# ic-mhm-encoder-v2.net
KiCad netlist of a schematic drawn in EAGLE
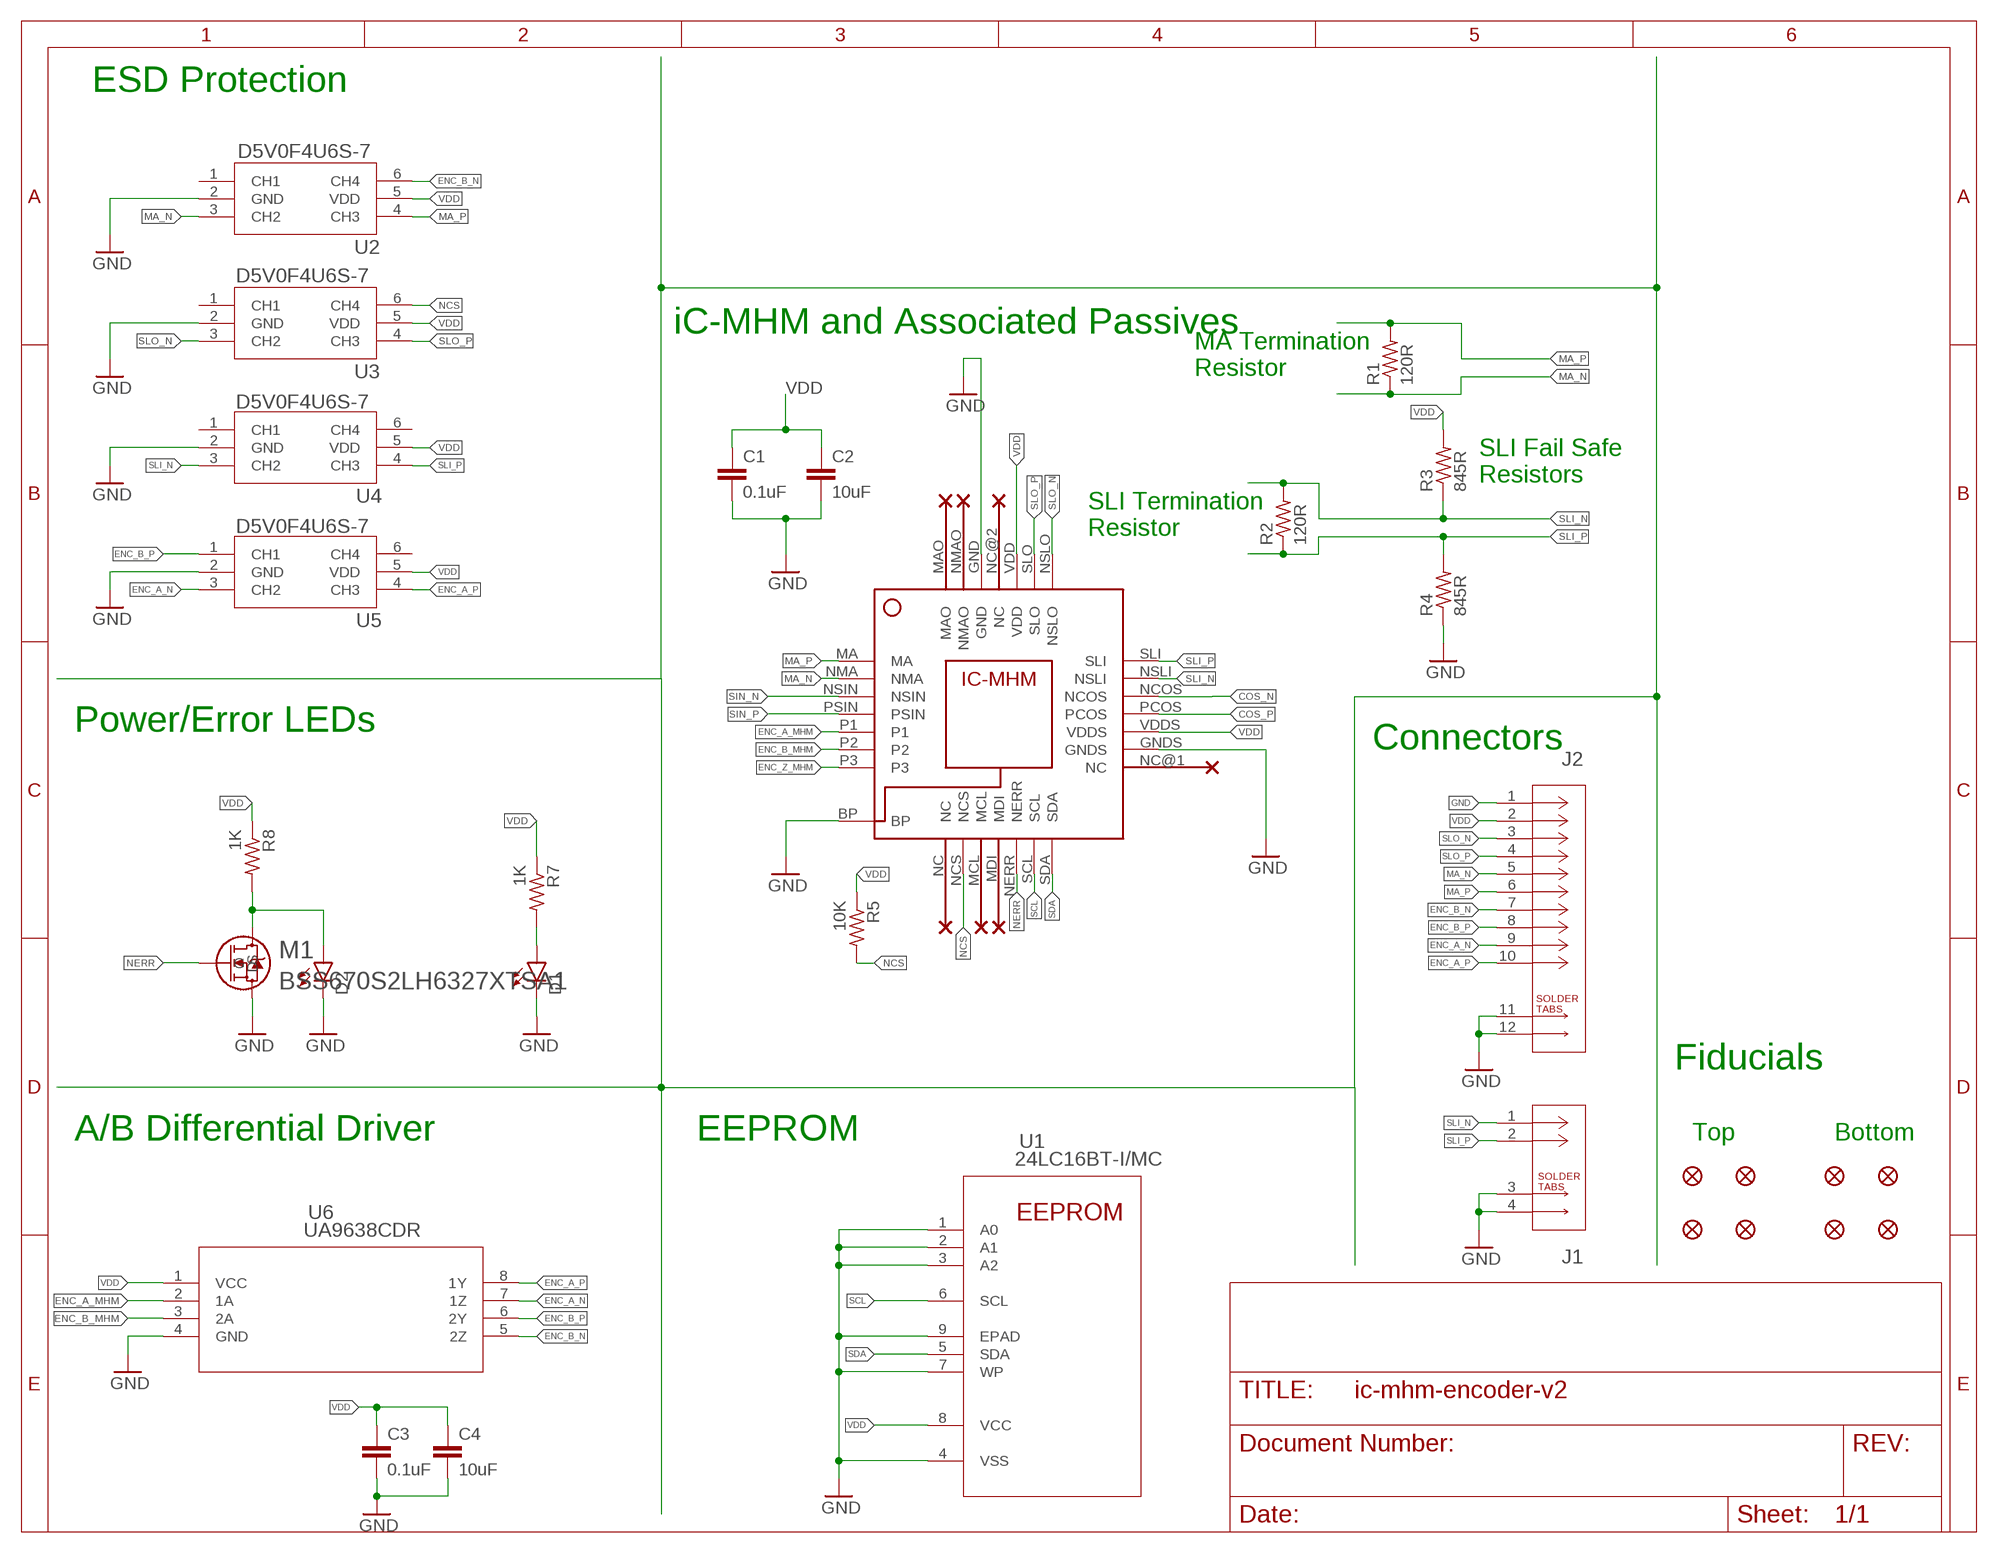
[diagram p0: schematic, sheet 1]

(export (version "E")
  (design (tool "Eeschema 10.0.6"))
  (components
    (comp (ref "C1")
      (value "0.1uF")
      (footprint "eagle-import:C0603")
      (libsource (lib "eagle-import") (part "C-EUC0603"))
    )
    (comp (ref "C2")
      (value "10uF")
      (footprint "eagle-import:C0603")
      (libsource (lib "eagle-import") (part "C-EUC0603"))
    )
    (comp (ref "C3")
      (value "0.1uF")
      (footprint "eagle-import:C0603")
      (libsource (lib "eagle-import") (part "C-EUC0603"))
    )
    (comp (ref "C4")
      (value "10uF")
      (footprint "eagle-import:C0603")
      (libsource (lib "eagle-import") (part "C-EUC0603"))
    )
    (comp (ref "D1")
      (value "LEDSML0603")
      (footprint "eagle-import:SML0603")
      (libsource (lib "eagle-import") (part "LEDSML0603"))
    )
    (comp (ref "D2")
      (value "LEDSML0603")
      (footprint "eagle-import:SML0603")
      (libsource (lib "eagle-import") (part "LEDSML0603"))
    )
    (comp (ref "FID1")
      (value "FIDUCIAL_1MM")
      (footprint "eagle-import:FIDUCIAL_1MM")
      (libsource (lib "eagle-import") (part "FIDUCIAL_1MM"))
    )
    (comp (ref "FID2")
      (value "FIDUCIAL_1MM")
      (footprint "eagle-import:FIDUCIAL_1MM")
      (libsource (lib "eagle-import") (part "FIDUCIAL_1MM"))
    )
    (comp (ref "FID3")
      (value "FIDUCIAL_1MM")
      (footprint "eagle-import:FIDUCIAL_1MM")
      (libsource (lib "eagle-import") (part "FIDUCIAL_1MM"))
    )
    (comp (ref "FID4")
      (value "FIDUCIAL_1MM")
      (footprint "eagle-import:FIDUCIAL_1MM")
      (libsource (lib "eagle-import") (part "FIDUCIAL_1MM"))
    )
    (comp (ref "FID5")
      (value "FIDUCIAL_1MM")
      (footprint "eagle-import:FIDUCIAL_1MM")
      (libsource (lib "eagle-import") (part "FIDUCIAL_1MM"))
    )
    (comp (ref "FID6")
      (value "FIDUCIAL_1MM")
      (footprint "eagle-import:FIDUCIAL_1MM")
      (libsource (lib "eagle-import") (part "FIDUCIAL_1MM"))
    )
    (comp (ref "FID7")
      (value "FIDUCIAL_1MM")
      (footprint "eagle-import:FIDUCIAL_1MM")
      (libsource (lib "eagle-import") (part "FIDUCIAL_1MM"))
    )
    (comp (ref "FID8")
      (value "FIDUCIAL_1MM")
      (footprint "eagle-import:FIDUCIAL_1MM")
      (libsource (lib "eagle-import") (part "FIDUCIAL_1MM"))
    )
    (comp (ref "J1")
      (value "2023960207")
      (footprint "eagle-import:CON_2023960207")
      (fields (field (name "COPYRIGHT") "Copyright (C) 2022 Ultra Librarian. All rights reserved."))
      (libsource (lib "eagle-import") (part "2023960207"))
    )
    (comp (ref "J2")
      (value "2023961007")
      (footprint "eagle-import:CON_2023961007")
      (fields (field (name "COPYRIGHT") "Copyright (C) 2022 Ultra Librarian. All rights reserved."))
      (libsource (lib "eagle-import") (part "2023961007"))
    )
    (comp (ref "M1")
      (value "BSS670S2LH6327XTSA1")
      (footprint "eagle-import:PG-SOT23-3-5_INF")
      (fields (field (name "COPYRIGHT") "Copyright (C) 2021 Ultra Librarian. All rights reserved."))
      (libsource (lib "eagle-import") (part "BSS670S2LH6327XTSA1"))
    )
    (comp (ref "R1")
      (value "120R")
      (footprint "eagle-import:R0603")
      (libsource (lib "eagle-import") (part "R-US_R0603"))
    )
    (comp (ref "R2")
      (value "120R")
      (footprint "eagle-import:R0603")
      (libsource (lib "eagle-import") (part "R-US_R0603"))
    )
    (comp (ref "R3")
      (value "845R")
      (footprint "eagle-import:R0603")
      (libsource (lib "eagle-import") (part "R-US_R0603"))
    )
    (comp (ref "R4")
      (value "845R")
      (footprint "eagle-import:R0603")
      (libsource (lib "eagle-import") (part "R-US_R0603"))
    )
    (comp (ref "R5")
      (value "10K")
      (footprint "eagle-import:R0603")
      (libsource (lib "eagle-import") (part "R-US_R0603"))
    )
    (comp (ref "R7")
      (value "1K")
      (footprint "eagle-import:R0603")
      (libsource (lib "eagle-import") (part "R-US_R0603"))
    )
    (comp (ref "R8")
      (value "1K")
      (footprint "eagle-import:R0603")
      (libsource (lib "eagle-import") (part "R-US_R0603"))
    )
    (comp (ref "U$1")
      (value "IC-MHM")
      (footprint "eagle-import:IC-MHM")
      (libsource (lib "eagle-import") (part "IC-MHM"))
    )
    (comp (ref "U1")
      (value "24LC16BT-I/MC")
      (footprint "eagle-import:DFN8_2X3MC_MCH")
      (fields (field (name "COPYRIGHT") "Copyright (C) 2021 Ultra Librarian. All rights reserved."))
      (libsource (lib "eagle-import") (part "24LC16BT-I/MC"))
    )
    (comp (ref "U2")
      (value "D5V0F4U6S-7")
      (footprint "eagle-import:SOT-363_DIO")
      (fields (field (name "COPYRIGHT") "Copyright (C) 2021 Ultra Librarian. All rights reserved."))
      (libsource (lib "eagle-import") (part "D5V0F4U6S-7"))
    )
    (comp (ref "U3")
      (value "D5V0F4U6S-7")
      (footprint "eagle-import:SOT-363_DIO")
      (fields (field (name "COPYRIGHT") "Copyright (C) 2021 Ultra Librarian. All rights reserved."))
      (libsource (lib "eagle-import") (part "D5V0F4U6S-7"))
    )
    (comp (ref "U4")
      (value "D5V0F4U6S-7")
      (footprint "eagle-import:SOT-363_DIO")
      (fields (field (name "COPYRIGHT") "Copyright (C) 2021 Ultra Librarian. All rights reserved."))
      (libsource (lib "eagle-import") (part "D5V0F4U6S-7"))
    )
    (comp (ref "U5")
      (value "D5V0F4U6S-7")
      (footprint "eagle-import:SOT-363_DIO")
      (fields (field (name "COPYRIGHT") "Copyright (C) 2021 Ultra Librarian. All rights reserved."))
      (libsource (lib "eagle-import") (part "D5V0F4U6S-7"))
    )
    (comp (ref "U6")
      (value "UA9638CDR")
      (footprint "eagle-import:D8")
      (fields (field (name "COPYRIGHT") "Copyright (C) 2022 Ultra Librarian. All rights reserved."))
      (libsource (lib "eagle-import") (part "UA9638CDR"))
    )
  )
  (nets
    (net (code "1") (name "COS_N") (class "Default")
      (node (ref "U$1") (pin "NCOS") (pinfunction "NCOS_NCOS") (pintype "bidirectional"))
    )
    (net (code "2") (name "COS_P") (class "Default")
      (node (ref "U$1") (pin "PCOS") (pinfunction "PCOS_PCOS") (pintype "bidirectional"))
    )
    (net (code "3") (name "ENC_A_MHM") (class "Default")
      (node (ref "U$1") (pin "P1") (pinfunction "P1_P1") (pintype "bidirectional"))
      (node (ref "U6") (pin "2") (pinfunction "1A_2") (pintype "passive"))
    )
    (net (code "4") (name "ENC_A_N") (class "Default")
      (node (ref "J2") (pin "9") (pinfunction "9_9") (pintype "passive"))
      (node (ref "U5") (pin "3") (pinfunction "CH2_3") (pintype "passive"))
      (node (ref "U6") (pin "7") (pinfunction "1Z_7") (pintype "output"))
    )
    (net (code "5") (name "ENC_A_P") (class "Default")
      (node (ref "J2") (pin "10") (pinfunction "10_10") (pintype "passive"))
      (node (ref "U5") (pin "4") (pinfunction "CH3_4") (pintype "passive"))
      (node (ref "U6") (pin "8") (pinfunction "1Y_8") (pintype "output"))
    )
    (net (code "6") (name "ENC_B_MHM") (class "Default")
      (node (ref "U$1") (pin "P2") (pinfunction "P2_P2") (pintype "bidirectional"))
      (node (ref "U6") (pin "3") (pinfunction "2A_3") (pintype "passive"))
    )
    (net (code "7") (name "ENC_B_N") (class "Default")
      (node (ref "J2") (pin "7") (pinfunction "7_7") (pintype "passive"))
      (node (ref "U2") (pin "6") (pinfunction "CH4_6") (pintype "passive"))
      (node (ref "U6") (pin "5") (pinfunction "2Z_5") (pintype "output"))
    )
    (net (code "8") (name "ENC_B_P") (class "Default")
      (node (ref "J2") (pin "8") (pinfunction "8_8") (pintype "passive"))
      (node (ref "U5") (pin "1") (pinfunction "CH1_1") (pintype "passive"))
      (node (ref "U6") (pin "6") (pinfunction "2Y_6") (pintype "output"))
    )
    (net (code "9") (name "ENC_Z_MHM") (class "Default")
      (node (ref "U$1") (pin "P3") (pinfunction "P3_P3") (pintype "bidirectional"))
    )
    (net (code "10") (name "GND") (class "Default")
      (node (ref "C1") (pin "2") (pinfunction "2_2") (pintype "passive"))
      (node (ref "C2") (pin "2") (pinfunction "2_2") (pintype "passive"))
      (node (ref "C3") (pin "2") (pinfunction "2_2") (pintype "passive"))
      (node (ref "C4") (pin "2") (pinfunction "2_2") (pintype "passive"))
      (node (ref "D1") (pin "C") (pinfunction "C_C") (pintype "passive"))
      (node (ref "D2") (pin "C") (pinfunction "C_C") (pintype "passive"))
      (node (ref "J1") (pin "3") (pinfunction "3_3") (pintype "passive"))
      (node (ref "J1") (pin "4") (pinfunction "4_4") (pintype "passive"))
      (node (ref "J2") (pin "1") (pinfunction "1_1") (pintype "passive"))
      (node (ref "J2") (pin "11") (pinfunction "11_11") (pintype "passive"))
      (node (ref "J2") (pin "12") (pinfunction "12_12") (pintype "passive"))
      (node (ref "M1") (pin "2") (pinfunction "S_2") (pintype "passive"))
      (node (ref "R4") (pin "1") (pinfunction "1_1") (pintype "passive"))
      (node (ref "U$1") (pin "BP") (pinfunction "BP_BP") (pintype "bidirectional"))
      (node (ref "U$1") (pin "GND") (pinfunction "GND_GND") (pintype "bidirectional"))
      (node (ref "U$1") (pin "GNDS") (pinfunction "GNDS_GNDS") (pintype "bidirectional"))
      (node (ref "U1") (pin "1") (pinfunction "A0_1") (pintype "input"))
      (node (ref "U1") (pin "2") (pinfunction "A1_2") (pintype "input"))
      (node (ref "U1") (pin "3") (pinfunction "A2_3") (pintype "input"))
      (node (ref "U1") (pin "4") (pinfunction "VSS_4") (pintype "power_in"))
      (node (ref "U1") (pin "7") (pinfunction "WP_7") (pintype "passive"))
      (node (ref "U1") (pin "9") (pinfunction "EPAD_9") (pintype "passive"))
      (node (ref "U2") (pin "2") (pinfunction "GND_2") (pintype "power_in"))
      (node (ref "U3") (pin "2") (pinfunction "GND_2") (pintype "power_in"))
      (node (ref "U4") (pin "2") (pinfunction "GND_2") (pintype "power_in"))
      (node (ref "U5") (pin "2") (pinfunction "GND_2") (pintype "power_in"))
      (node (ref "U6") (pin "4") (pinfunction "GND_4") (pintype "power_in"))
    )
    (net (code "11") (name "MA_N") (class "Default")
      (node (ref "J2") (pin "5") (pinfunction "5_5") (pintype "passive"))
      (node (ref "R1") (pin "1") (pinfunction "1_1") (pintype "passive"))
      (node (ref "U$1") (pin "NMA") (pinfunction "NMA_NMA") (pintype "bidirectional"))
      (node (ref "U2") (pin "3") (pinfunction "CH2_3") (pintype "passive"))
    )
    (net (code "12") (name "MA_P") (class "Default")
      (node (ref "J2") (pin "6") (pinfunction "6_6") (pintype "passive"))
      (node (ref "R1") (pin "2") (pinfunction "2_2") (pintype "passive"))
      (node (ref "U$1") (pin "MA") (pinfunction "MA_MA") (pintype "bidirectional"))
      (node (ref "U2") (pin "4") (pinfunction "CH3_4") (pintype "passive"))
    )
    (net (code "13") (name "NCS") (class "Default")
      (node (ref "R5") (pin "2") (pinfunction "2_2") (pintype "passive"))
      (node (ref "U$1") (pin "NCS") (pinfunction "NCS_NCS") (pintype "bidirectional"))
      (node (ref "U3") (pin "6") (pinfunction "CH4_6") (pintype "passive"))
    )
    (net (code "14") (name "NERR") (class "Default")
      (node (ref "M1") (pin "1") (pinfunction "G_1") (pintype "passive"))
      (node (ref "U$1") (pin "NERR") (pinfunction "NERR_NERR") (pintype "bidirectional"))
    )
    (net (code "15") (name "Net-(D1-PadA)") (class "Default")
      (node (ref "D1") (pin "A") (pinfunction "A_A") (pintype "passive"))
      (node (ref "R7") (pin "2") (pinfunction "2_2") (pintype "passive"))
    )
    (net (code "16") (name "Net-(M1-D)") (class "Default")
      (node (ref "D2") (pin "A") (pinfunction "A_A") (pintype "passive"))
      (node (ref "M1") (pin "3") (pinfunction "D_3") (pintype "passive"))
      (node (ref "R8") (pin "2") (pinfunction "2_2") (pintype "passive"))
    )
    (net (code "17") (name "SCL") (class "Default")
      (node (ref "U$1") (pin "SCL") (pinfunction "SCL_SCL") (pintype "bidirectional"))
      (node (ref "U1") (pin "6") (pinfunction "SCL_6") (pintype "input"))
    )
    (net (code "18") (name "SDA") (class "Default")
      (node (ref "U$1") (pin "SDA") (pinfunction "SDA_SDA") (pintype "bidirectional"))
      (node (ref "U1") (pin "5") (pinfunction "SDA_5") (pintype "bidirectional"))
    )
    (net (code "19") (name "SIN_N") (class "Default")
      (node (ref "U$1") (pin "NSIN") (pinfunction "NSIN_NSIN") (pintype "bidirectional"))
    )
    (net (code "20") (name "SIN_P") (class "Default")
      (node (ref "U$1") (pin "PSIN") (pinfunction "PSIN_PSIN") (pintype "bidirectional"))
    )
    (net (code "21") (name "SLI_N") (class "Default")
      (node (ref "J1") (pin "1") (pinfunction "1_1") (pintype "passive"))
      (node (ref "R2") (pin "2") (pinfunction "2_2") (pintype "passive"))
      (node (ref "R3") (pin "1") (pinfunction "1_1") (pintype "passive"))
      (node (ref "U$1") (pin "NSLI") (pinfunction "NSLI_NSLI") (pintype "bidirectional"))
      (node (ref "U4") (pin "3") (pinfunction "CH2_3") (pintype "passive"))
    )
    (net (code "22") (name "SLI_P") (class "Default")
      (node (ref "J1") (pin "2") (pinfunction "2_2") (pintype "passive"))
      (node (ref "R2") (pin "1") (pinfunction "1_1") (pintype "passive"))
      (node (ref "R4") (pin "2") (pinfunction "2_2") (pintype "passive"))
      (node (ref "U$1") (pin "SLI") (pinfunction "SLI_SLI") (pintype "bidirectional"))
      (node (ref "U4") (pin "4") (pinfunction "CH3_4") (pintype "passive"))
    )
    (net (code "23") (name "SLO_N") (class "Default")
      (node (ref "J2") (pin "3") (pinfunction "3_3") (pintype "passive"))
      (node (ref "U$1") (pin "NSLO") (pinfunction "NSLO_NSLO") (pintype "bidirectional"))
      (node (ref "U3") (pin "3") (pinfunction "CH2_3") (pintype "passive"))
    )
    (net (code "24") (name "SLO_P") (class "Default")
      (node (ref "J2") (pin "4") (pinfunction "4_4") (pintype "passive"))
      (node (ref "U$1") (pin "SLO") (pinfunction "SLO_SLO") (pintype "bidirectional"))
      (node (ref "U3") (pin "4") (pinfunction "CH3_4") (pintype "passive"))
    )
    (net (code "25") (name "VDD") (class "Default")
      (node (ref "C1") (pin "1") (pinfunction "1_1") (pintype "passive"))
      (node (ref "C2") (pin "1") (pinfunction "1_1") (pintype "passive"))
      (node (ref "C3") (pin "1") (pinfunction "1_1") (pintype "passive"))
      (node (ref "C4") (pin "1") (pinfunction "1_1") (pintype "passive"))
      (node (ref "J2") (pin "2") (pinfunction "2_2") (pintype "passive"))
      (node (ref "R3") (pin "2") (pinfunction "2_2") (pintype "passive"))
      (node (ref "R5") (pin "1") (pinfunction "1_1") (pintype "passive"))
      (node (ref "R7") (pin "1") (pinfunction "1_1") (pintype "passive"))
      (node (ref "R8") (pin "1") (pinfunction "1_1") (pintype "passive"))
      (node (ref "U$1") (pin "VDD") (pinfunction "VDD_VDD") (pintype "bidirectional"))
      (node (ref "U$1") (pin "VDDS") (pinfunction "VDDS_VDDS") (pintype "bidirectional"))
      (node (ref "U1") (pin "8") (pinfunction "VCC_8") (pintype "power_in"))
      (node (ref "U2") (pin "5") (pinfunction "VDD_5") (pintype "power_in"))
      (node (ref "U3") (pin "5") (pinfunction "VDD_5") (pintype "power_in"))
      (node (ref "U4") (pin "5") (pinfunction "VDD_5") (pintype "power_in"))
      (node (ref "U5") (pin "5") (pinfunction "VDD_5") (pintype "power_in"))
      (node (ref "U6") (pin "1") (pinfunction "VCC_1") (pintype "power_in"))
    )
    (net (code "26") (name "unconnected-(U$1-NC-PadNC@1)") (class "Default")
      (node (ref "U$1") (pin "NC@1") (pinfunction "NC_NC@1") (pintype "bidirectional"))
    )
    (net (code "27") (name "unconnected-(U$1-NC-PadNC@2)") (class "Default")
      (node (ref "U$1") (pin "NC@2") (pinfunction "NC_NC@2") (pintype "bidirectional"))
    )
    (net (code "28") (name "unconnected-(U$1-PadMAO)") (class "Default")
      (node (ref "U$1") (pin "MAO") (pinfunction "MAO_MAO") (pintype "bidirectional"))
    )
    (net (code "29") (name "unconnected-(U$1-PadMCL)") (class "Default")
      (node (ref "U$1") (pin "MCL") (pinfunction "MCL_MCL") (pintype "bidirectional"))
    )
    (net (code "30") (name "unconnected-(U$1-PadMDI)") (class "Default")
      (node (ref "U$1") (pin "MDI") (pinfunction "MDI_MDI") (pintype "bidirectional"))
    )
    (net (code "31") (name "unconnected-(U$1-PadNC)") (class "Default")
      (node (ref "U$1") (pin "NC") (pinfunction "NC_NC") (pintype "bidirectional"))
    )
    (net (code "32") (name "unconnected-(U$1-PadNMAO)") (class "Default")
      (node (ref "U$1") (pin "NMAO") (pinfunction "NMAO_NMAO") (pintype "bidirectional"))
    )
    (net (code "33") (name "unconnected-(U2-CH1-Pad1)") (class "Default")
      (node (ref "U2") (pin "1") (pinfunction "CH1_1") (pintype "passive"))
    )
    (net (code "34") (name "unconnected-(U3-CH1-Pad1)") (class "Default")
      (node (ref "U3") (pin "1") (pinfunction "CH1_1") (pintype "passive"))
    )
    (net (code "35") (name "unconnected-(U4-CH1-Pad1)") (class "Default")
      (node (ref "U4") (pin "1") (pinfunction "CH1_1") (pintype "passive"))
    )
    (net (code "36") (name "unconnected-(U4-CH4-Pad6)") (class "Default")
      (node (ref "U4") (pin "6") (pinfunction "CH4_6") (pintype "passive"))
    )
    (net (code "37") (name "unconnected-(U5-CH4-Pad6)") (class "Default")
      (node (ref "U5") (pin "6") (pinfunction "CH4_6") (pintype "passive"))
    )
  )
)
